# giraffe20.net
KiCad netlist of a schematic drawn in EAGLE
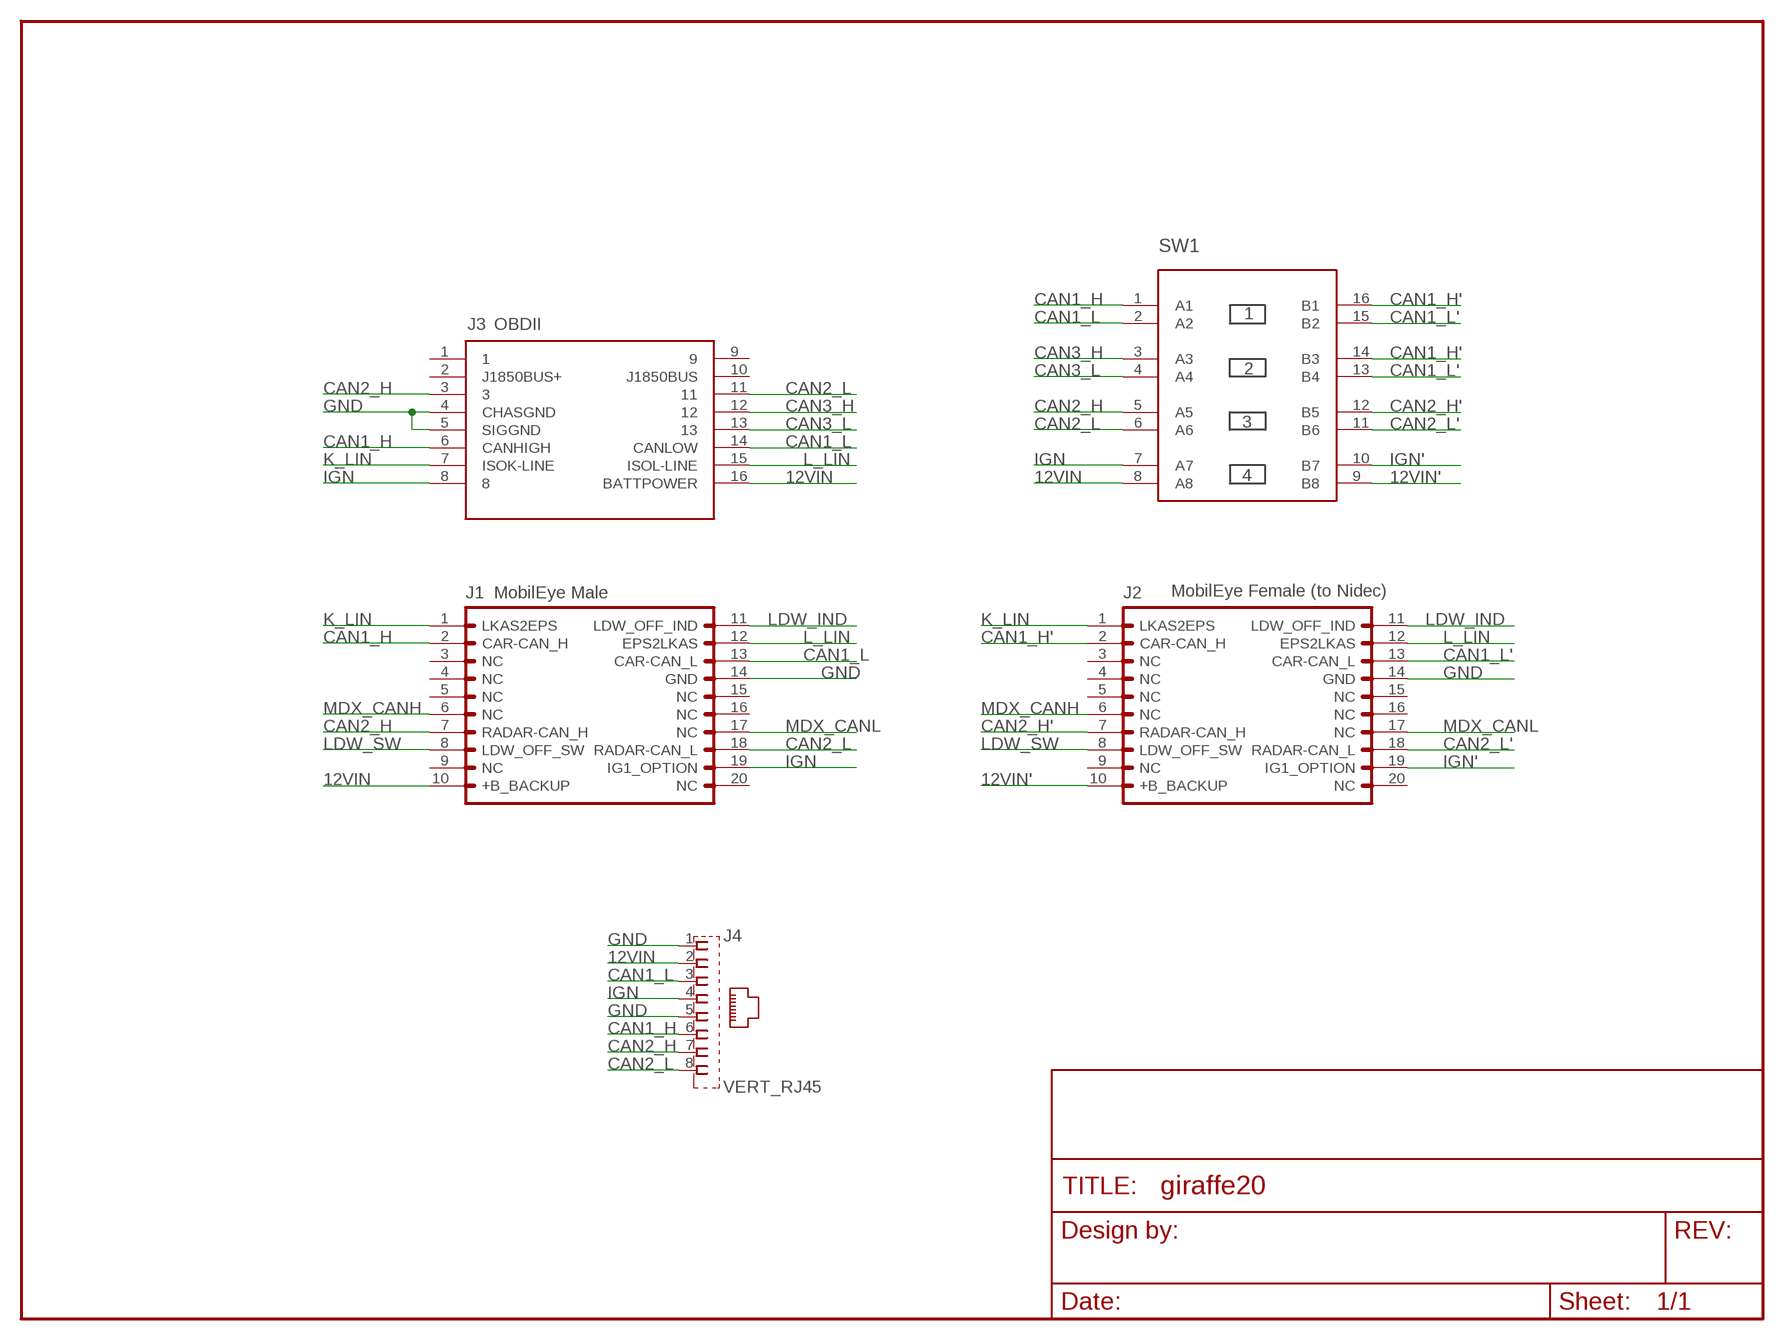
[diagram p0: schematic, sheet 1]

(export (version "E")
  (design (tool "Eeschema 10.0.6"))
  (components
    (comp (ref "FRAME1")
      (value "FRAME-LETTERNO_PACKAGE")
      (footprint "eagle-import:DUMMY")
      (fields (field (name "DESIGNER") "Nobody"))
      (libsource (lib "eagle-import") (part "FRAME-LETTERNO_PACKAGE"))
    )
    (comp (ref "J1")
      (value "MOBILEYERAMALE")
      (footprint "eagle-import:2X10(RA)")
      (libsource (lib "eagle-import") (part "MOBILEYERAMALE"))
    )
    (comp (ref "J2")
      (value "MOBILEYEFEMALE")
      (footprint "eagle-import:2X10(JAE_FEMALE)")
      (libsource (lib "eagle-import") (part "MOBILEYEFEMALE"))
    )
    (comp (ref "J3")
      (value "OBDII-FEMALE-CUT")
      (footprint "eagle-import:OBDII-FEMALE-MIDCUT")
      (libsource (lib "eagle-import") (part "OBDII-FEMALE-CUT"))
    )
    (comp (ref "J4")
      (value "VERT_RJ45")
      (footprint "eagle-import:GLX-S-88M")
      (libsource (lib "eagle-import") (part "VERT_RJ45"))
    )
    (comp (ref "SW1")
      (value "4XDPSTSMT")
      (footprint "eagle-import:4-DPST")
      (libsource (lib "eagle-import") (part "4XDPSTSMT"))
    )
  )
  (nets
    (net (code "1") (name "/12VIN") (class "Default")
      (node (ref "J1") (pin "10") (pinfunction "+B_BACKUP_10") (pintype "bidirectional"))
      (node (ref "J3") (pin "16") (pinfunction "BATTPOWER_16") (pintype "bidirectional"))
      (node (ref "J4") (pin "2") (pinfunction "2_2") (pintype "passive"))
      (node (ref "SW1") (pin "8") (pinfunction "A8_8") (pintype "bidirectional"))
    )
    (net (code "2") (name "/12VIN'") (class "Default")
      (node (ref "J2") (pin "10") (pinfunction "+B_BACKUP_10") (pintype "bidirectional"))
      (node (ref "SW1") (pin "9") (pinfunction "B8_9") (pintype "bidirectional"))
    )
    (net (code "3") (name "/CAN1_H") (class "Default")
      (node (ref "J1") (pin "2") (pinfunction "CAR-CAN_H_2") (pintype "bidirectional"))
      (node (ref "J3") (pin "6") (pinfunction "CANHIGH_6") (pintype "bidirectional"))
      (node (ref "J4") (pin "6") (pinfunction "6_6") (pintype "passive"))
      (node (ref "SW1") (pin "1") (pinfunction "A1_1") (pintype "bidirectional"))
    )
    (net (code "4") (name "/CAN1_H'") (class "Default")
      (node (ref "J2") (pin "2") (pinfunction "CAR-CAN_H_2") (pintype "bidirectional"))
      (node (ref "SW1") (pin "14") (pinfunction "B3_14") (pintype "bidirectional"))
      (node (ref "SW1") (pin "16") (pinfunction "B1_16") (pintype "bidirectional"))
    )
    (net (code "5") (name "/CAN1_L") (class "Default")
      (node (ref "J1") (pin "13") (pinfunction "CAR-CAN_L_13") (pintype "bidirectional"))
      (node (ref "J3") (pin "14") (pinfunction "CANLOW_14") (pintype "bidirectional"))
      (node (ref "J4") (pin "3") (pinfunction "3_3") (pintype "passive"))
      (node (ref "SW1") (pin "2") (pinfunction "A2_2") (pintype "bidirectional"))
    )
    (net (code "6") (name "/CAN1_L'") (class "Default")
      (node (ref "J2") (pin "13") (pinfunction "CAR-CAN_L_13") (pintype "bidirectional"))
      (node (ref "SW1") (pin "13") (pinfunction "B4_13") (pintype "bidirectional"))
      (node (ref "SW1") (pin "15") (pinfunction "B2_15") (pintype "bidirectional"))
    )
    (net (code "7") (name "/CAN2_H") (class "Default")
      (node (ref "J1") (pin "7") (pinfunction "RADAR-CAN_H_7") (pintype "bidirectional"))
      (node (ref "J3") (pin "3") (pinfunction "3_3") (pintype "bidirectional"))
      (node (ref "J4") (pin "7") (pinfunction "7_7") (pintype "passive"))
      (node (ref "SW1") (pin "5") (pinfunction "A5_5") (pintype "bidirectional"))
    )
    (net (code "8") (name "/CAN2_H'") (class "Default")
      (node (ref "J2") (pin "7") (pinfunction "RADAR-CAN_H_7") (pintype "bidirectional"))
      (node (ref "SW1") (pin "12") (pinfunction "B5_12") (pintype "bidirectional"))
    )
    (net (code "9") (name "/CAN2_L") (class "Default")
      (node (ref "J1") (pin "18") (pinfunction "RADAR-CAN_L_18") (pintype "bidirectional"))
      (node (ref "J3") (pin "11") (pinfunction "11_11") (pintype "bidirectional"))
      (node (ref "J4") (pin "8") (pinfunction "8_8") (pintype "passive"))
      (node (ref "SW1") (pin "6") (pinfunction "A6_6") (pintype "bidirectional"))
    )
    (net (code "10") (name "/CAN2_L'") (class "Default")
      (node (ref "J2") (pin "18") (pinfunction "RADAR-CAN_L_18") (pintype "bidirectional"))
      (node (ref "SW1") (pin "11") (pinfunction "B6_11") (pintype "bidirectional"))
    )
    (net (code "11") (name "/CAN3_H") (class "Default")
      (node (ref "J3") (pin "12") (pinfunction "12_12") (pintype "bidirectional"))
      (node (ref "SW1") (pin "3") (pinfunction "A3_3") (pintype "bidirectional"))
    )
    (net (code "12") (name "/CAN3_L") (class "Default")
      (node (ref "J3") (pin "13") (pinfunction "13_13") (pintype "bidirectional"))
      (node (ref "SW1") (pin "4") (pinfunction "A4_4") (pintype "bidirectional"))
    )
    (net (code "13") (name "/GND") (class "Default")
      (node (ref "J1") (pin "14") (pinfunction "GND_14") (pintype "bidirectional"))
      (node (ref "J2") (pin "14") (pinfunction "GND_14") (pintype "bidirectional"))
      (node (ref "J3") (pin "4") (pinfunction "CHASGND_4") (pintype "bidirectional"))
      (node (ref "J3") (pin "5") (pinfunction "SIGGND_5") (pintype "bidirectional"))
      (node (ref "J4") (pin "1") (pinfunction "1_1") (pintype "passive"))
      (node (ref "J4") (pin "5") (pinfunction "5_5") (pintype "passive"))
    )
    (net (code "14") (name "/IGN") (class "Default")
      (node (ref "J1") (pin "19") (pinfunction "IG1_OPTION_19") (pintype "bidirectional"))
      (node (ref "J3") (pin "8") (pinfunction "8_8") (pintype "bidirectional"))
      (node (ref "J4") (pin "4") (pinfunction "4_4") (pintype "passive"))
      (node (ref "SW1") (pin "7") (pinfunction "A7_7") (pintype "bidirectional"))
    )
    (net (code "15") (name "/IGN'") (class "Default")
      (node (ref "J2") (pin "19") (pinfunction "IG1_OPTION_19") (pintype "bidirectional"))
      (node (ref "SW1") (pin "10") (pinfunction "B7_10") (pintype "bidirectional"))
    )
    (net (code "16") (name "/K_LIN") (class "Default")
      (node (ref "J1") (pin "1") (pinfunction "LKAS2EPS_1") (pintype "bidirectional"))
      (node (ref "J2") (pin "1") (pinfunction "LKAS2EPS_1") (pintype "bidirectional"))
      (node (ref "J3") (pin "7") (pinfunction "ISOK-LINE_7") (pintype "bidirectional"))
    )
    (net (code "17") (name "/LDW_IND") (class "Default")
      (node (ref "J1") (pin "11") (pinfunction "LDW_OFF_IND_11") (pintype "bidirectional"))
      (node (ref "J2") (pin "11") (pinfunction "LDW_OFF_IND_11") (pintype "bidirectional"))
    )
    (net (code "18") (name "/LDW_SW") (class "Default")
      (node (ref "J1") (pin "8") (pinfunction "LDW_OFF_SW_8") (pintype "bidirectional"))
      (node (ref "J2") (pin "8") (pinfunction "LDW_OFF_SW_8") (pintype "bidirectional"))
    )
    (net (code "19") (name "/L_LIN") (class "Default")
      (node (ref "J1") (pin "12") (pinfunction "EPS2LKAS_12") (pintype "bidirectional"))
      (node (ref "J2") (pin "12") (pinfunction "EPS2LKAS_12") (pintype "bidirectional"))
      (node (ref "J3") (pin "15") (pinfunction "ISOL-LINE_15") (pintype "bidirectional"))
    )
    (net (code "20") (name "/MDX_CANH") (class "Default")
      (node (ref "J1") (pin "6") (pinfunction "NC_6") (pintype "bidirectional"))
      (node (ref "J2") (pin "6") (pinfunction "NC_6") (pintype "bidirectional"))
    )
    (net (code "21") (name "/MDX_CANL") (class "Default")
      (node (ref "J1") (pin "17") (pinfunction "NC_17") (pintype "bidirectional"))
      (node (ref "J2") (pin "17") (pinfunction "NC_17") (pintype "bidirectional"))
    )
    (net (code "22") (name "unconnected-(J1-NC-Pad3)") (class "Default")
      (node (ref "J1") (pin "3") (pinfunction "NC_3") (pintype "bidirectional"))
    )
    (net (code "23") (name "unconnected-(J1-NC-Pad4)") (class "Default")
      (node (ref "J1") (pin "4") (pinfunction "NC_4") (pintype "bidirectional"))
    )
    (net (code "24") (name "unconnected-(J1-NC-Pad5)") (class "Default")
      (node (ref "J1") (pin "5") (pinfunction "NC_5") (pintype "bidirectional"))
    )
    (net (code "25") (name "unconnected-(J1-NC-Pad9)") (class "Default")
      (node (ref "J1") (pin "9") (pinfunction "NC_9") (pintype "bidirectional"))
    )
    (net (code "26") (name "unconnected-(J1-NC-Pad15)") (class "Default")
      (node (ref "J1") (pin "15") (pinfunction "NC_15") (pintype "bidirectional"))
    )
    (net (code "27") (name "unconnected-(J1-NC-Pad16)") (class "Default")
      (node (ref "J1") (pin "16") (pinfunction "NC_16") (pintype "bidirectional"))
    )
    (net (code "28") (name "unconnected-(J1-NC-Pad20)") (class "Default")
      (node (ref "J1") (pin "20") (pinfunction "NC_20") (pintype "bidirectional"))
    )
    (net (code "29") (name "unconnected-(J2-NC-Pad3)") (class "Default")
      (node (ref "J2") (pin "3") (pinfunction "NC_3") (pintype "bidirectional"))
    )
    (net (code "30") (name "unconnected-(J2-NC-Pad4)") (class "Default")
      (node (ref "J2") (pin "4") (pinfunction "NC_4") (pintype "bidirectional"))
    )
    (net (code "31") (name "unconnected-(J2-NC-Pad5)") (class "Default")
      (node (ref "J2") (pin "5") (pinfunction "NC_5") (pintype "bidirectional"))
    )
    (net (code "32") (name "unconnected-(J2-NC-Pad9)") (class "Default")
      (node (ref "J2") (pin "9") (pinfunction "NC_9") (pintype "bidirectional"))
    )
    (net (code "33") (name "unconnected-(J2-NC-Pad15)") (class "Default")
      (node (ref "J2") (pin "15") (pinfunction "NC_15") (pintype "bidirectional"))
    )
    (net (code "34") (name "unconnected-(J2-NC-Pad16)") (class "Default")
      (node (ref "J2") (pin "16") (pinfunction "NC_16") (pintype "bidirectional"))
    )
    (net (code "35") (name "unconnected-(J2-NC-Pad20)") (class "Default")
      (node (ref "J2") (pin "20") (pinfunction "NC_20") (pintype "bidirectional"))
    )
    (net (code "36") (name "unconnected-(J3-J1850BUS+-Pad2)") (class "Default")
      (node (ref "J3") (pin "2") (pinfunction "J1850BUS+_2") (pintype "bidirectional"))
    )
    (net (code "37") (name "unconnected-(J3-J1850BUS-Pad10)") (class "Default")
      (node (ref "J3") (pin "10") (pinfunction "J1850BUS_10") (pintype "bidirectional"))
    )
    (net (code "38") (name "unconnected-(J3-Pad1)") (class "Default")
      (node (ref "J3") (pin "1") (pinfunction "1_1") (pintype "bidirectional"))
    )
    (net (code "39") (name "unconnected-(J3-Pad9)") (class "Default")
      (node (ref "J3") (pin "9") (pinfunction "9_9") (pintype "bidirectional"))
    )
  )
)
